# design.net
KiCad netlist of a schematic drawn in Altium Designer
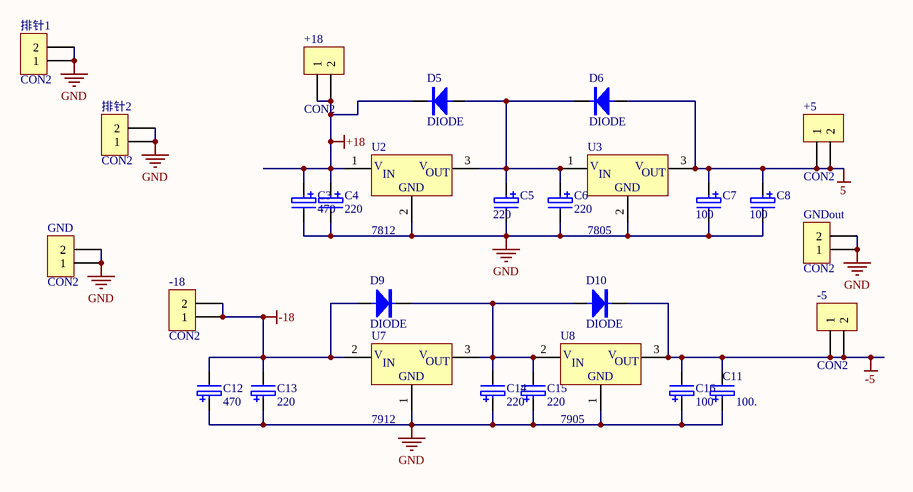
[diagram p0: 单片机供电.SchDoc]

(export (version "E")
  (design (tool "Eeschema 10.0.6"))
  (components
    (comp (ref "+5")
      (value "CON2")
      (footprint "2P-200")
      (description "Connector")
      (libsource (lib "") (part "CON2_1"))
    )
    (comp (ref "+18")
      (value "CON2")
      (footprint "2P-200")
      (description "Connector")
      (libsource (lib "") (part "CON2_1"))
    )
    (comp (ref "-5")
      (value "CON2")
      (footprint "2P-200")
      (description "Connector")
      (libsource (lib "") (part "CON2_1"))
    )
    (comp (ref "-18")
      (value "CON2")
      (footprint "2P-200")
      (description "Connector")
      (libsource (lib "接口") (part "CON2"))
    )
    (comp (ref "C3") (value "470") (footprint "CAO4") (libsource (lib "电容") (part "CAP3")))
    (comp (ref "C4") (value "220") (footprint "CAO4") (libsource (lib "电容") (part "CAP3")))
    (comp (ref "C5") (value "220") (footprint "CAO4") (libsource (lib "电容") (part "CAP3")))
    (comp (ref "C6") (value "220") (footprint "CAO4") (libsource (lib "电容") (part "CAP3")))
    (comp (ref "C7") (value "100") (footprint "CAO4") (libsource (lib "电容") (part "CAP3")))
    (comp (ref "C8") (value "100") (footprint "CAO4") (libsource (lib "电容") (part "CAP3")))
    (comp (ref "C11") (value "100.") (footprint "CAO4") (libsource (lib "电容") (part "CAP3")))
    (comp (ref "C12") (value "470") (footprint "CAO4") (libsource (lib "电容") (part "CAP3")))
    (comp (ref "C13") (value "220") (footprint "CAO4") (libsource (lib "电容") (part "CAP3")))
    (comp (ref "C14") (value "220") (footprint "CAO4") (libsource (lib "电容") (part "CAP3")))
    (comp (ref "C15") (value "220") (footprint "CAO4") (libsource (lib "电容") (part "CAP3")))
    (comp (ref "C16") (value "100") (footprint "CAO4") (libsource (lib "电容") (part "CAP3")))
    (comp (ref "D5") (value "DIODE") (footprint "DIODE0.4") (libsource (lib "二极管") (part "DIODE")))
    (comp (ref "D6") (value "DIODE") (footprint "DIODE0.4") (libsource (lib "二极管") (part "DIODE")))
    (comp (ref "D9") (value "DIODE") (footprint "DIODE0.4") (libsource (lib "") (part "DIODE_1")))
    (comp (ref "D10") (value "DIODE") (footprint "DIODE0.4") (libsource (lib "") (part "DIODE_1")))
    (comp (ref "GND")
      (value "CON2")
      (footprint "2P-200")
      (description "Connector")
      (libsource (lib "接口") (part "CON2"))
    )
    (comp (ref "GNDout")
      (value "CON2")
      (footprint "2P-200")
      (description "Connector")
      (libsource (lib "接口") (part "CON2"))
    )
    (comp (ref "U2")
      (value "7812")
      (footprint "TO-220")
      (description "3-Terminal Positive Voltage Regulator")
      (libsource (lib "稳压器件") (part "78LXX"))
    )
    (comp (ref "U3")
      (value "7805")
      (footprint "TO-220")
      (description "3-Terminal Positive Voltage Regulator")
      (libsource (lib "稳压器件") (part "78LXX"))
    )
    (comp (ref "U7") (value "7912") (footprint "TO-220") (libsource (lib "稳压器件") (part "79LXX")))
    (comp (ref "U8") (value "7905") (footprint "TO-220") (libsource (lib "稳压器件") (part "79LXX")))
    (comp (ref "排针1")
      (value "CON2")
      (footprint "sip-2")
      (description "Connector")
      (libsource (lib "接口") (part "CON2"))
    )
    (comp (ref "排针2")
      (value "CON2")
      (footprint "sip-2")
      (description "Connector")
      (libsource (lib "接口") (part "CON2"))
    )
  )
  (nets
    (net (code "1") (name "+18") (class "Default")
      (node (ref "+18") (pin "1") (pinfunction "1_1") (pintype "passive"))
      (node (ref "+18") (pin "2") (pinfunction "2_2") (pintype "passive"))
      (node (ref "C3") (pin "1") (pintype "passive"))
      (node (ref "C4") (pin "1") (pintype "passive"))
      (node (ref "D5") (pin "2") (pinfunction "2_2") (pintype "passive"))
      (node (ref "U2") (pin "1") (pinfunction "VIN_1") (pintype "passive"))
    )
    (net (code "2") (name "-5") (class "Default")
      (node (ref "-5") (pin "1") (pinfunction "1_1") (pintype "passive"))
      (node (ref "-5") (pin "2") (pinfunction "2_2") (pintype "passive"))
      (node (ref "C11") (pin "2") (pintype "passive"))
      (node (ref "C16") (pin "2") (pintype "passive"))
      (node (ref "D10") (pin "2") (pinfunction "2_2") (pintype "passive"))
      (node (ref "U8") (pin "3") (pinfunction "VOUT_3") (pintype "passive"))
    )
    (net (code "3") (name "-18") (class "Default")
      (node (ref "-18") (pin "1") (pinfunction "1_1") (pintype "passive"))
      (node (ref "-18") (pin "2") (pinfunction "2_2") (pintype "passive"))
      (node (ref "C12") (pin "2") (pintype "passive"))
      (node (ref "C13") (pin "2") (pintype "passive"))
      (node (ref "D9") (pin "1") (pinfunction "1_1") (pintype "passive"))
      (node (ref "U7") (pin "2") (pinfunction "VIN_2") (pintype "passive"))
    )
    (net (code "4") (name "5") (class "Default")
      (node (ref "+5") (pin "1") (pinfunction "1_1") (pintype "passive"))
      (node (ref "+5") (pin "2") (pinfunction "2_2") (pintype "passive"))
      (node (ref "C7") (pin "1") (pintype "passive"))
      (node (ref "C8") (pin "1") (pintype "passive"))
      (node (ref "D6") (pin "1") (pinfunction "1_1") (pintype "passive"))
      (node (ref "U3") (pin "3") (pinfunction "VOUT_3") (pintype "passive"))
    )
    (net (code "5") (name "GND") (class "Default")
      (node (ref "C11") (pin "1") (pintype "passive"))
      (node (ref "C12") (pin "1") (pintype "passive"))
      (node (ref "C13") (pin "1") (pintype "passive"))
      (node (ref "C14") (pin "1") (pintype "passive"))
      (node (ref "C15") (pin "1") (pintype "passive"))
      (node (ref "C16") (pin "1") (pintype "passive"))
      (node (ref "C3") (pin "2") (pintype "passive"))
      (node (ref "C4") (pin "2") (pintype "passive"))
      (node (ref "C5") (pin "2") (pintype "passive"))
      (node (ref "C6") (pin "2") (pintype "passive"))
      (node (ref "C7") (pin "2") (pintype "passive"))
      (node (ref "C8") (pin "2") (pintype "passive"))
      (node (ref "GND") (pin "1") (pinfunction "1_1") (pintype "passive"))
      (node (ref "GND") (pin "2") (pinfunction "2_2") (pintype "passive"))
      (node (ref "GNDout") (pin "1") (pinfunction "1_1") (pintype "passive"))
      (node (ref "GNDout") (pin "2") (pinfunction "2_2") (pintype "passive"))
      (node (ref "U2") (pin "2") (pinfunction "GND_2") (pintype "passive"))
      (node (ref "U3") (pin "2") (pinfunction "GND_2") (pintype "passive"))
      (node (ref "U7") (pin "1") (pinfunction "GND_1") (pintype "passive"))
      (node (ref "U8") (pin "1") (pinfunction "GND_1") (pintype "passive"))
      (node (ref "排针1") (pin "1") (pinfunction "1_1") (pintype "passive"))
      (node (ref "排针1") (pin "2") (pinfunction "2_2") (pintype "passive"))
      (node (ref "排针2") (pin "1") (pinfunction "1_1") (pintype "passive"))
      (node (ref "排针2") (pin "2") (pinfunction "2_2") (pintype "passive"))
    )
    (net (code "6") (name "Net-(U2-VOUT)") (class "Default")
      (node (ref "C5") (pin "1") (pintype "passive"))
      (node (ref "C6") (pin "1") (pintype "passive"))
      (node (ref "D5") (pin "1") (pinfunction "1_1") (pintype "passive"))
      (node (ref "D6") (pin "2") (pinfunction "2_2") (pintype "passive"))
      (node (ref "U2") (pin "3") (pinfunction "VOUT_3") (pintype "passive"))
      (node (ref "U3") (pin "1") (pinfunction "VIN_1") (pintype "passive"))
    )
    (net (code "7") (name "Net-(U7-VOUT)") (class "Default")
      (node (ref "C14") (pin "2") (pintype "passive"))
      (node (ref "C15") (pin "2") (pintype "passive"))
      (node (ref "D10") (pin "1") (pinfunction "1_1") (pintype "passive"))
      (node (ref "D9") (pin "2") (pinfunction "2_2") (pintype "passive"))
      (node (ref "U7") (pin "3") (pinfunction "VOUT_3") (pintype "passive"))
      (node (ref "U8") (pin "2") (pinfunction "VIN_2") (pintype "passive"))
    )
  )
)
